# STM8S003_-OSH.net
KiCad netlist of a schematic drawn in EAGLE
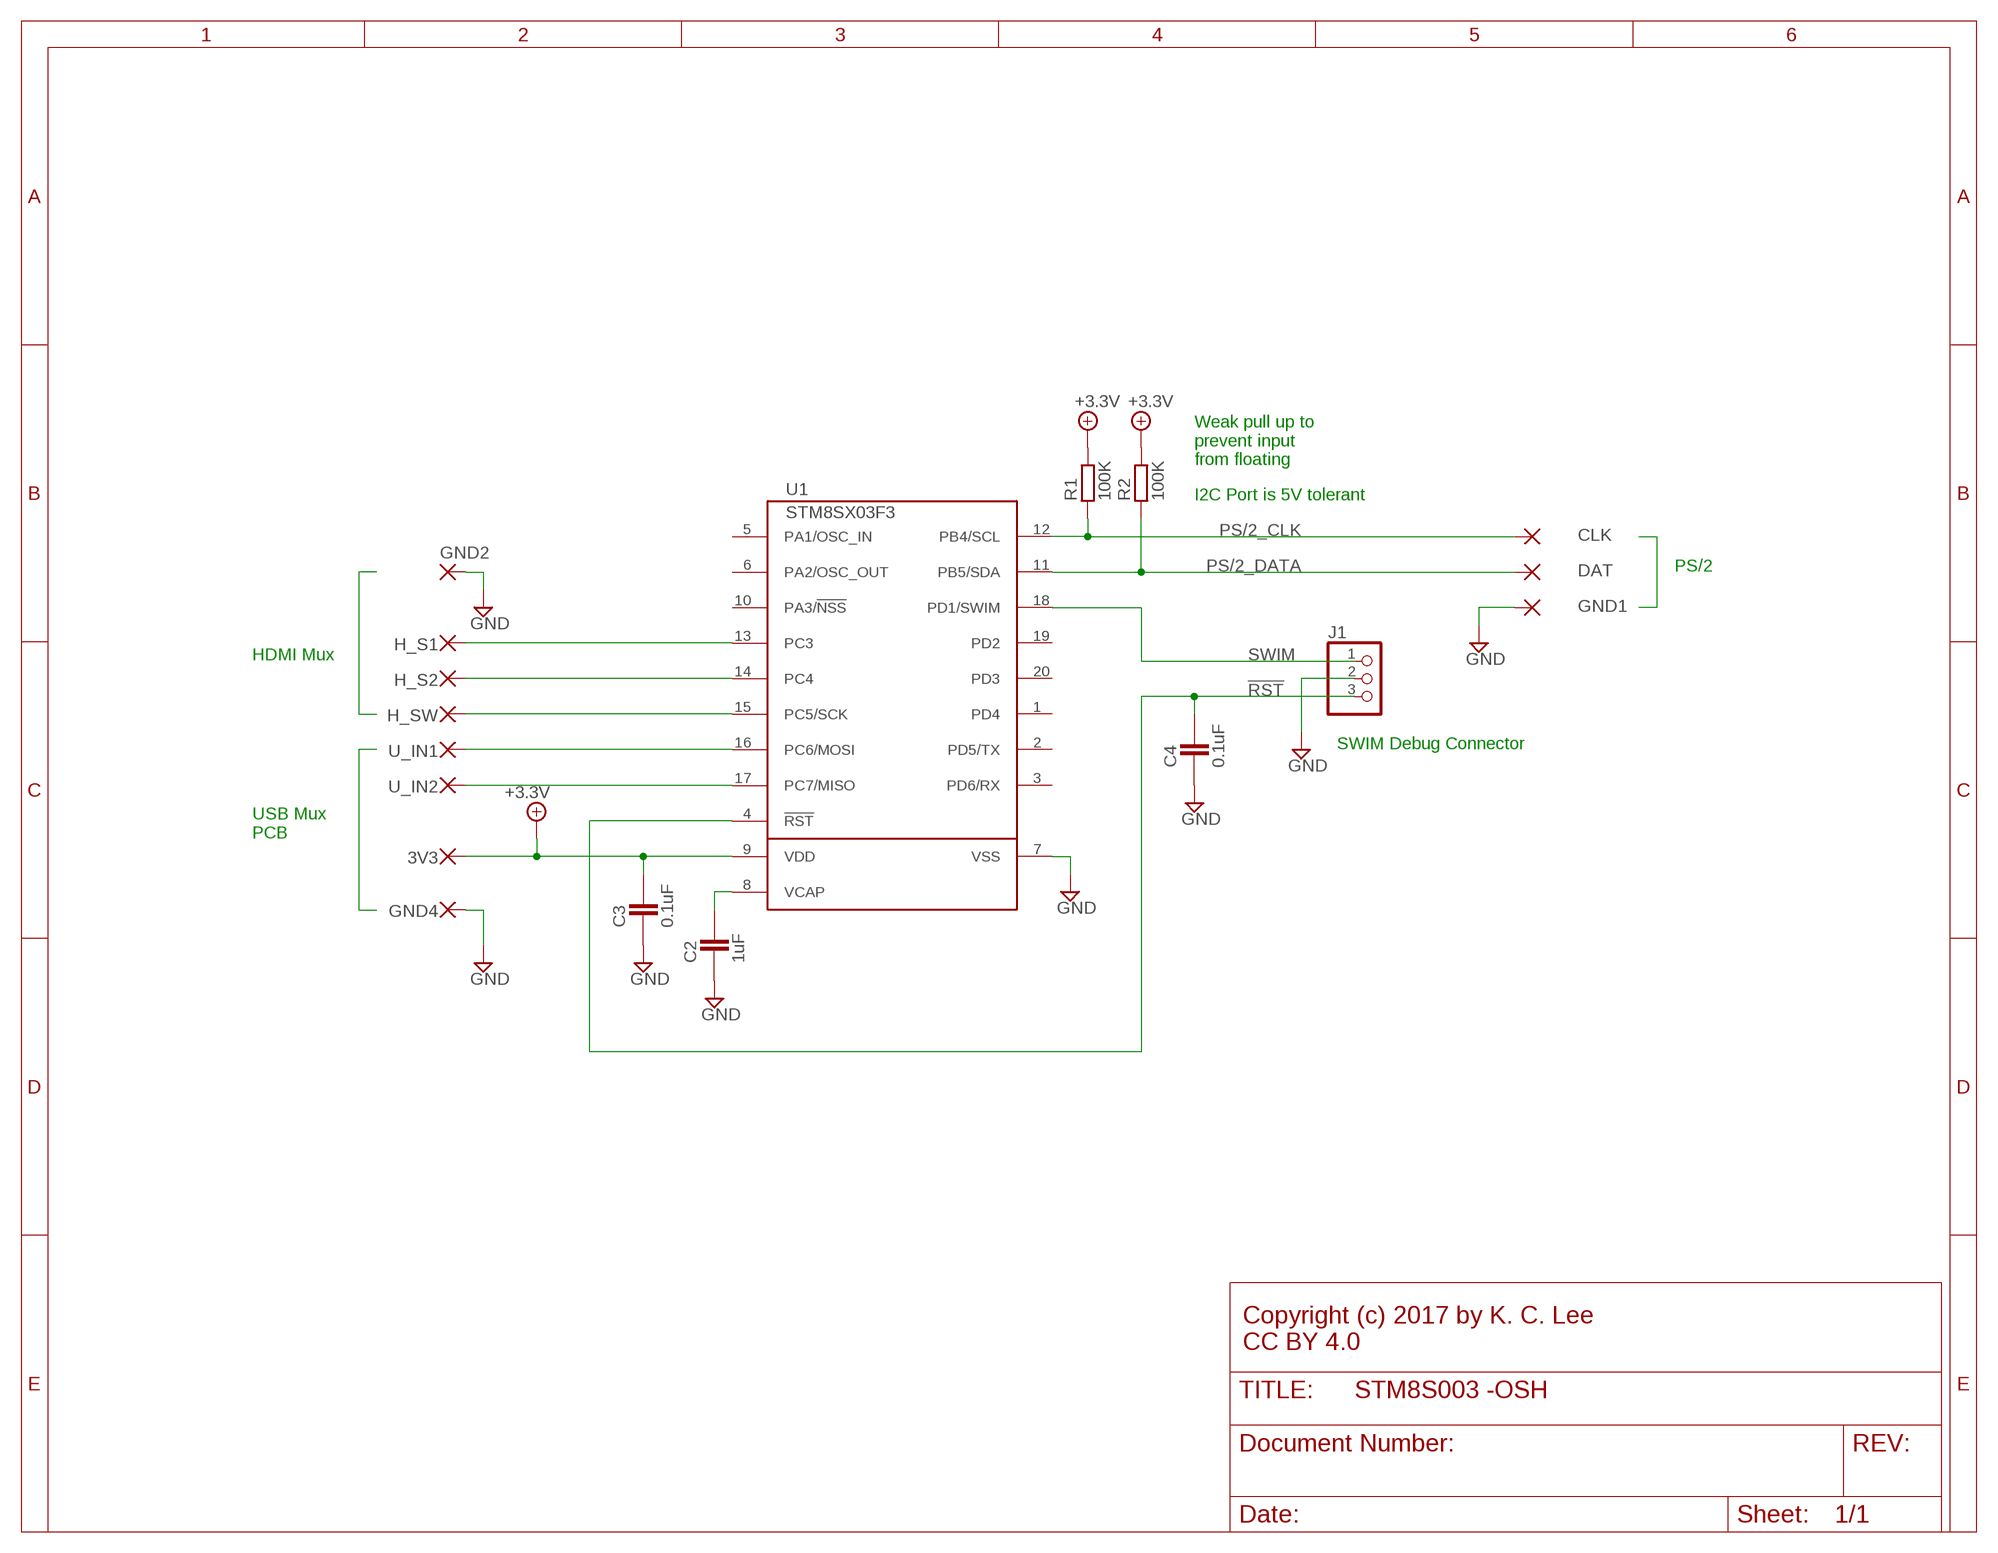
[diagram p0: schematic, sheet 1]

(export (version "E")
  (design (tool "Eeschema 10.0.6"))
  (components
    (comp (ref "3V3")
      (value "SMD2")
      (footprint "eagle-import:SMD1,27-2,54")
      (libsource (lib "eagle-import") (part "SMD2"))
    )
    (comp (ref "C2")
      (value "1uF")
      (footprint "eagle-import:CAPC1608X92N")
      (libsource (lib "eagle-import") (part "CAPACITOR_0603"))
    )
    (comp (ref "C3")
      (value "0.1uF")
      (footprint "eagle-import:CAPC1608X92N")
      (libsource (lib "eagle-import") (part "CAPACITOR_0603"))
    )
    (comp (ref "C4")
      (value "0.1uF")
      (footprint "eagle-import:CAPC1608X92N")
      (libsource (lib "eagle-import") (part "CAPACITOR_0603"))
    )
    (comp (ref "CLK")
      (value "SMD2")
      (footprint "eagle-import:SMD1,27-2,54")
      (libsource (lib "eagle-import") (part "SMD2"))
    )
    (comp (ref "DAT")
      (value "SMD2")
      (footprint "eagle-import:SMD1,27-2,54")
      (libsource (lib "eagle-import") (part "SMD2"))
    )
    (comp (ref "GND1")
      (value "SMD2")
      (footprint "eagle-import:SMD1,27-2,54")
      (libsource (lib "eagle-import") (part "SMD2"))
    )
    (comp (ref "GND2")
      (value "SMD2")
      (footprint "eagle-import:SMD1,27-2,54")
      (libsource (lib "eagle-import") (part "SMD2"))
    )
    (comp (ref "GND4")
      (value "SMD2")
      (footprint "eagle-import:SMD1,27-2,54")
      (libsource (lib "eagle-import") (part "SMD2"))
    )
    (comp (ref "H_S1")
      (value "SMD2")
      (footprint "eagle-import:SMD1,27-2,54")
      (libsource (lib "eagle-import") (part "SMD2"))
    )
    (comp (ref "H_S2")
      (value "SMD2")
      (footprint "eagle-import:SMD1,27-2,54")
      (libsource (lib "eagle-import") (part "SMD2"))
    )
    (comp (ref "H_SW")
      (value "SMD2")
      (footprint "eagle-import:SMD1,27-2,54")
      (libsource (lib "eagle-import") (part "SMD2"))
    )
    (comp (ref "J1")
      (value "PINHD-1X3")
      (footprint "eagle-import:1X03")
      (libsource (lib "eagle-import") (part "PINHD-1X3"))
    )
    (comp (ref "R1")
      (value "100K")
      (footprint "eagle-import:RESC1608X55N")
      (libsource (lib "eagle-import") (part "RESISTOR_0603"))
    )
    (comp (ref "R2")
      (value "100K")
      (footprint "eagle-import:RESC1608X55N")
      (libsource (lib "eagle-import") (part "RESISTOR_0603"))
    )
    (comp (ref "U1")
      (value "STM8SX03F3")
      (footprint "eagle-import:TSSOP20")
      (libsource (lib "eagle-import") (part "STM8SX03F3"))
    )
    (comp (ref "U_IN1")
      (value "SMD2")
      (footprint "eagle-import:SMD1,27-2,54")
      (libsource (lib "eagle-import") (part "SMD2"))
    )
    (comp (ref "U_IN2")
      (value "SMD2")
      (footprint "eagle-import:SMD1,27-2,54")
      (libsource (lib "eagle-import") (part "SMD2"))
    )
  )
  (nets
    (net (code "1") (name "+3.3V") (class "Default")
      (node (ref "3V3") (pin "1") (pinfunction "P_1") (pintype "passive"))
      (node (ref "C3") (pin "2") (pinfunction "2_2") (pintype "passive"))
      (node (ref "R1") (pin "2") (pinfunction "2_2") (pintype "passive"))
      (node (ref "R2") (pin "2") (pinfunction "2_2") (pintype "passive"))
      (node (ref "U1") (pin "9") (pinfunction "VDD_9") (pintype "input"))
    )
    (net (code "2") (name "/PS{slash}2_CLK") (class "Default")
      (node (ref "CLK") (pin "1") (pinfunction "P_1") (pintype "passive"))
      (node (ref "R1") (pin "1") (pinfunction "1_1") (pintype "passive"))
      (node (ref "U1") (pin "12") (pinfunction "PB4/SCL_12") (pintype "bidirectional"))
    )
    (net (code "3") (name "/PS{slash}2_DATA") (class "Default")
      (node (ref "DAT") (pin "1") (pinfunction "P_1") (pintype "passive"))
      (node (ref "R2") (pin "1") (pinfunction "1_1") (pintype "passive"))
      (node (ref "U1") (pin "11") (pinfunction "PB5/SDA_11") (pintype "bidirectional"))
    )
    (net (code "4") (name "/SWIM") (class "Default")
      (node (ref "J1") (pin "1") (pinfunction "1_1") (pintype "passive"))
      (node (ref "U1") (pin "18") (pinfunction "PD1/SWIM_18") (pintype "input"))
    )
    (net (code "5") (name "/~{RST}") (class "Default")
      (node (ref "C4") (pin "2") (pinfunction "2_2") (pintype "passive"))
      (node (ref "J1") (pin "3") (pinfunction "3_3") (pintype "passive"))
      (node (ref "U1") (pin "4") (pinfunction "~{RST}_4") (pintype "input"))
    )
    (net (code "6") (name "GND") (class "Default")
      (node (ref "C2") (pin "1") (pinfunction "1_1") (pintype "passive"))
      (node (ref "C3") (pin "1") (pinfunction "1_1") (pintype "passive"))
      (node (ref "C4") (pin "1") (pinfunction "1_1") (pintype "passive"))
      (node (ref "GND1") (pin "1") (pinfunction "P_1") (pintype "passive"))
      (node (ref "GND2") (pin "1") (pinfunction "P_1") (pintype "passive"))
      (node (ref "GND4") (pin "1") (pinfunction "P_1") (pintype "passive"))
      (node (ref "J1") (pin "2") (pinfunction "2_2") (pintype "passive"))
      (node (ref "U1") (pin "7") (pinfunction "VSS_7") (pintype "input"))
    )
    (net (code "7") (name "Net-(H_S1-P)") (class "Default")
      (node (ref "H_S1") (pin "1") (pinfunction "P_1") (pintype "passive"))
      (node (ref "U1") (pin "13") (pinfunction "PC3_13") (pintype "bidirectional"))
    )
    (net (code "8") (name "Net-(H_S2-P)") (class "Default")
      (node (ref "H_S2") (pin "1") (pinfunction "P_1") (pintype "passive"))
      (node (ref "U1") (pin "14") (pinfunction "PC4_14") (pintype "bidirectional"))
    )
    (net (code "9") (name "Net-(H_SW-P)") (class "Default")
      (node (ref "H_SW") (pin "1") (pinfunction "P_1") (pintype "passive"))
      (node (ref "U1") (pin "15") (pinfunction "PC5/SCK_15") (pintype "bidirectional"))
    )
    (net (code "10") (name "Net-(U1-PC6{slash}MOSI)") (class "Default")
      (node (ref "U1") (pin "16") (pinfunction "PC6/MOSI_16") (pintype "bidirectional"))
      (node (ref "U_IN1") (pin "1") (pinfunction "P_1") (pintype "passive"))
    )
    (net (code "11") (name "Net-(U1-PC7{slash}MISO)") (class "Default")
      (node (ref "U1") (pin "17") (pinfunction "PC7/MISO_17") (pintype "bidirectional"))
      (node (ref "U_IN2") (pin "1") (pinfunction "P_1") (pintype "passive"))
    )
    (net (code "12") (name "Net-(U1-VCAP)") (class "Default")
      (node (ref "C2") (pin "2") (pinfunction "2_2") (pintype "passive"))
      (node (ref "U1") (pin "8") (pinfunction "VCAP_8") (pintype "input"))
    )
    (net (code "13") (name "unconnected-(U1-PA1{slash}OSC_IN-Pad5)") (class "Default")
      (node (ref "U1") (pin "5") (pinfunction "PA1/OSC_IN_5") (pintype "input"))
    )
    (net (code "14") (name "unconnected-(U1-PA2{slash}OSC_OUT-Pad6)") (class "Default")
      (node (ref "U1") (pin "6") (pinfunction "PA2/OSC_OUT_6") (pintype "output"))
    )
    (net (code "15") (name "unconnected-(U1-PA3{slash}~{NSS}-Pad10)") (class "Default")
      (node (ref "U1") (pin "10") (pinfunction "PA3/~{NSS}_10") (pintype "bidirectional"))
    )
    (net (code "16") (name "unconnected-(U1-PD2-Pad19)") (class "Default")
      (node (ref "U1") (pin "19") (pinfunction "PD2_19") (pintype "bidirectional"))
    )
    (net (code "17") (name "unconnected-(U1-PD3-Pad20)") (class "Default")
      (node (ref "U1") (pin "20") (pinfunction "PD3_20") (pintype "bidirectional"))
    )
    (net (code "18") (name "unconnected-(U1-PD4-Pad1)") (class "Default")
      (node (ref "U1") (pin "1") (pinfunction "PD4_1") (pintype "bidirectional"))
    )
    (net (code "19") (name "unconnected-(U1-PD5{slash}TX-Pad2)") (class "Default")
      (node (ref "U1") (pin "2") (pinfunction "PD5/TX_2") (pintype "bidirectional"))
    )
    (net (code "20") (name "unconnected-(U1-PD6{slash}RX-Pad3)") (class "Default")
      (node (ref "U1") (pin "3") (pinfunction "PD6/RX_3") (pintype "bidirectional"))
    )
  )
)
